# Sheet1.net
KiCad netlist of a schematic drawn in Altium Designer
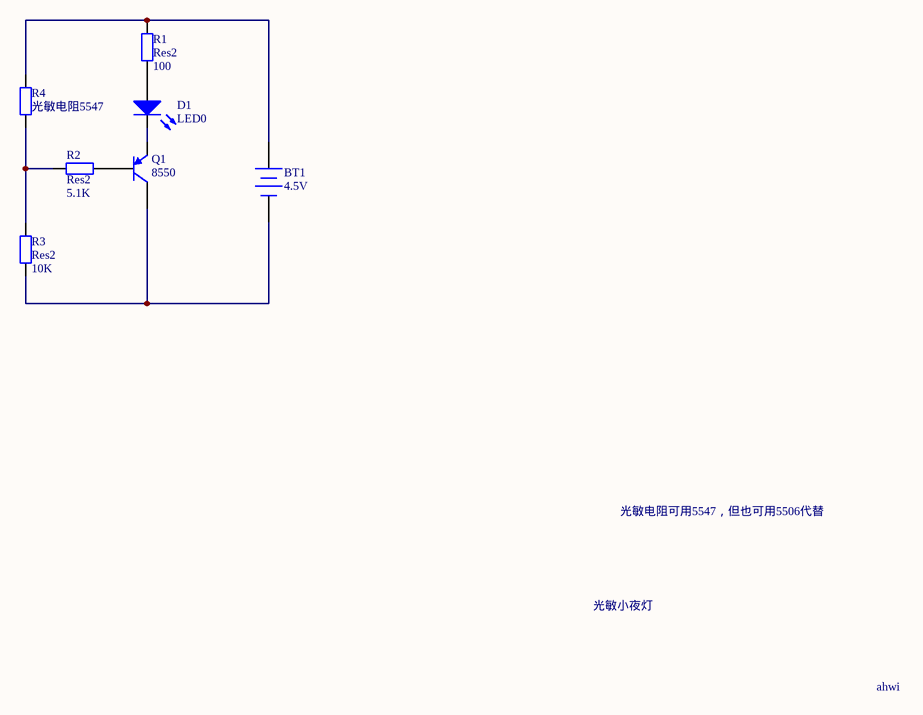
[diagram p0: Sheet1.SchDoc]

(export (version "E")
  (design (tool "Eeschema 10.0.6"))
  (components
    (comp (ref "BT1")
      (value "4.5V")
      (footprint "BAT-2")
      (description "Multicell Battery")
      (fields (field (name "PUBLISHER") "Altium Limited"))
      (libsource (lib "Miscellaneous Devices") (part "Battery"))
    )
    (comp (ref "D1")
      (value "LED0")
      (footprint "LED-0")
      (description "Typical INFRARED GaAs LED")
      (fields (field (name "PUBLISHER") "Altium Limited"))
      (libsource (lib "Miscellaneous Devices") (part "LED0"))
    )
    (comp (ref "Q1")
      (value "8550")
      (footprint "SOT-23B_N")
      (description "PNP Bipolar Transistor")
      (fields (field (name "PUBLISHER") "Altium Limited"))
      (libsource (lib "Miscellaneous Devices") (part "PNP"))
    )
    (comp (ref "R1")
      (value "Res2")
      (footprint "AXIAL-0.4")
      (description "Resistor")
      (fields (field (name "ALTIUM_VALUE") "100") (field (name "PUBLISHER") "Altium Limited"))
      (libsource (lib "Miscellaneous Devices") (part "Res2"))
    )
    (comp (ref "R2")
      (value "Res2")
      (footprint "AXIAL-0.4")
      (description "Resistor")
      (fields (field (name "ALTIUM_VALUE") "5.1K") (field (name "PUBLISHER") "Altium Limited"))
      (libsource (lib "") (part "Res2_1"))
    )
    (comp (ref "R3")
      (value "Res2")
      (footprint "AXIAL-0.4")
      (description "Resistor")
      (fields (field (name "ALTIUM_VALUE") "10K") (field (name "PUBLISHER") "Altium Limited"))
      (libsource (lib "Miscellaneous Devices") (part "Res2"))
    )
    (comp (ref "R4")
      (value "光敏电阻5547")
      (footprint "AXIAL-0.4")
      (description "Resistor")
      (fields (field (name "PUBLISHER") "Altium Limited"))
      (libsource (lib "Miscellaneous Devices") (part "Res2"))
    )
  )
  (nets
    (net (code "1") (name "Net-(BT1-+)") (class "Default")
      (node (ref "BT1") (pin "1") (pinfunction "+_1") (pintype "passive"))
      (node (ref "R1") (pin "2") (pinfunction "2_2") (pintype "passive"))
      (node (ref "R4") (pin "2") (pinfunction "2_2") (pintype "passive"))
    )
    (net (code "2") (name "Net-(BT1--)") (class "Default")
      (node (ref "BT1") (pin "2") (pinfunction "-_2") (pintype "passive"))
      (node (ref "Q1") (pin "1") (pinfunction "C_1") (pintype "passive"))
      (node (ref "R3") (pin "1") (pinfunction "1_1") (pintype "passive"))
    )
    (net (code "3") (name "Net-(D1-A)") (class "Default")
      (node (ref "D1") (pin "1") (pinfunction "A_1") (pintype "passive"))
      (node (ref "R1") (pin "1") (pinfunction "1_1") (pintype "passive"))
    )
    (net (code "4") (name "Net-(D1-K)") (class "Default")
      (node (ref "D1") (pin "2") (pinfunction "K_2") (pintype "passive"))
      (node (ref "Q1") (pin "3") (pinfunction "E_3") (pintype "passive"))
    )
    (net (code "5") (name "Net-(Q1-B)") (class "Default")
      (node (ref "Q1") (pin "2") (pinfunction "B_2") (pintype "passive"))
      (node (ref "R2") (pin "2") (pinfunction "2_2") (pintype "passive"))
    )
    (net (code "6") (name "Net-(R2-Pad1)") (class "Default")
      (node (ref "R2") (pin "1") (pinfunction "1_1") (pintype "passive"))
      (node (ref "R3") (pin "2") (pinfunction "2_2") (pintype "passive"))
      (node (ref "R4") (pin "1") (pinfunction "1_1") (pintype "passive"))
    )
  )
)
